# espnative-deadrail-2-d.net
KiCad netlist of a schematic drawn in EAGLE
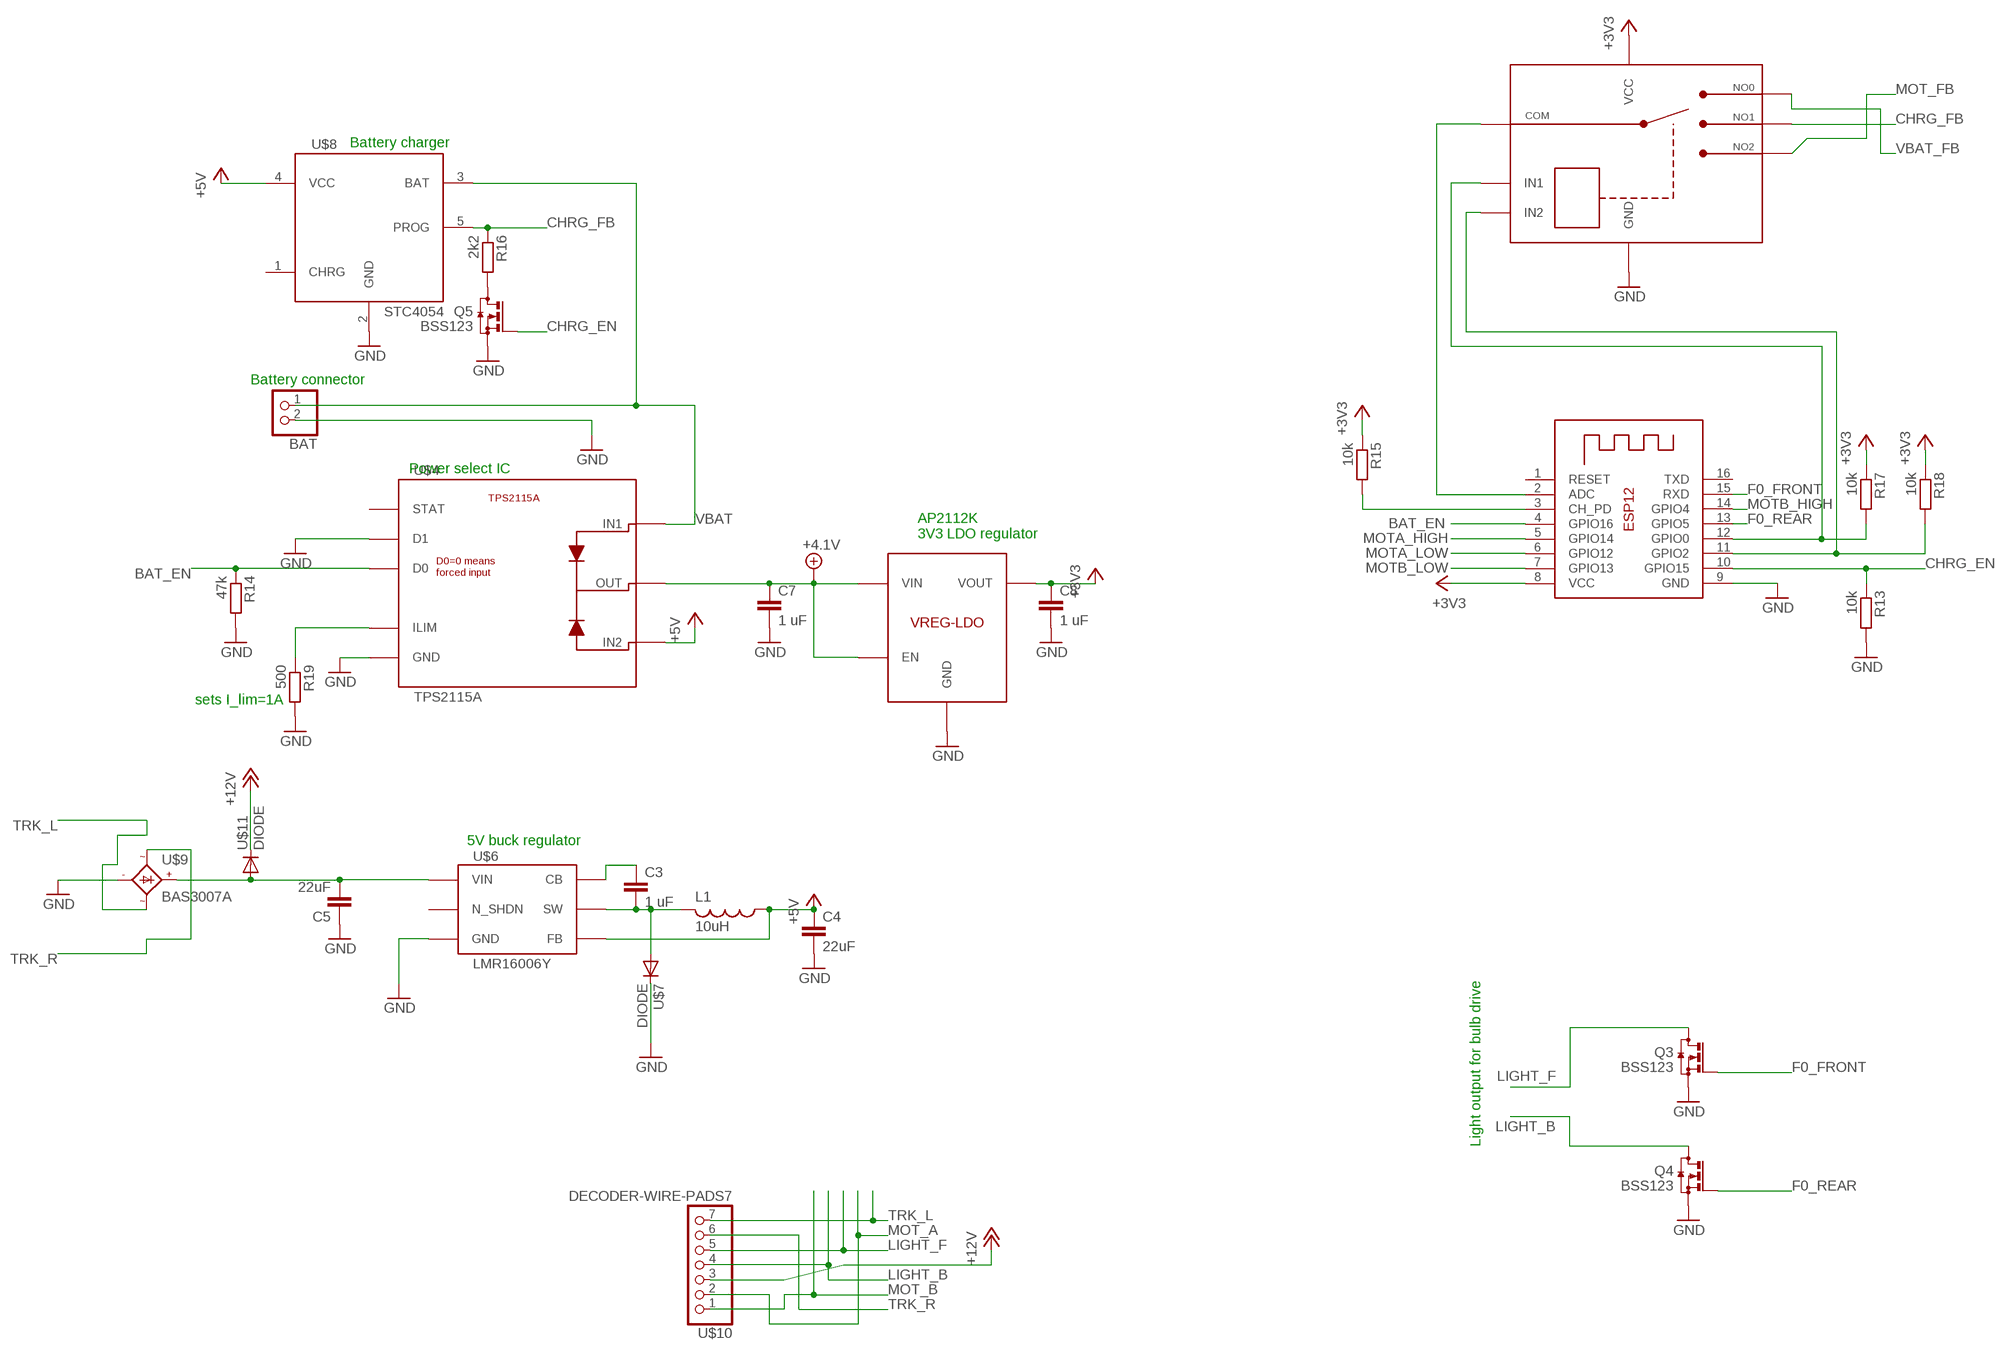
[diagram p0: schematic, sheet 1, part 1 of 2]
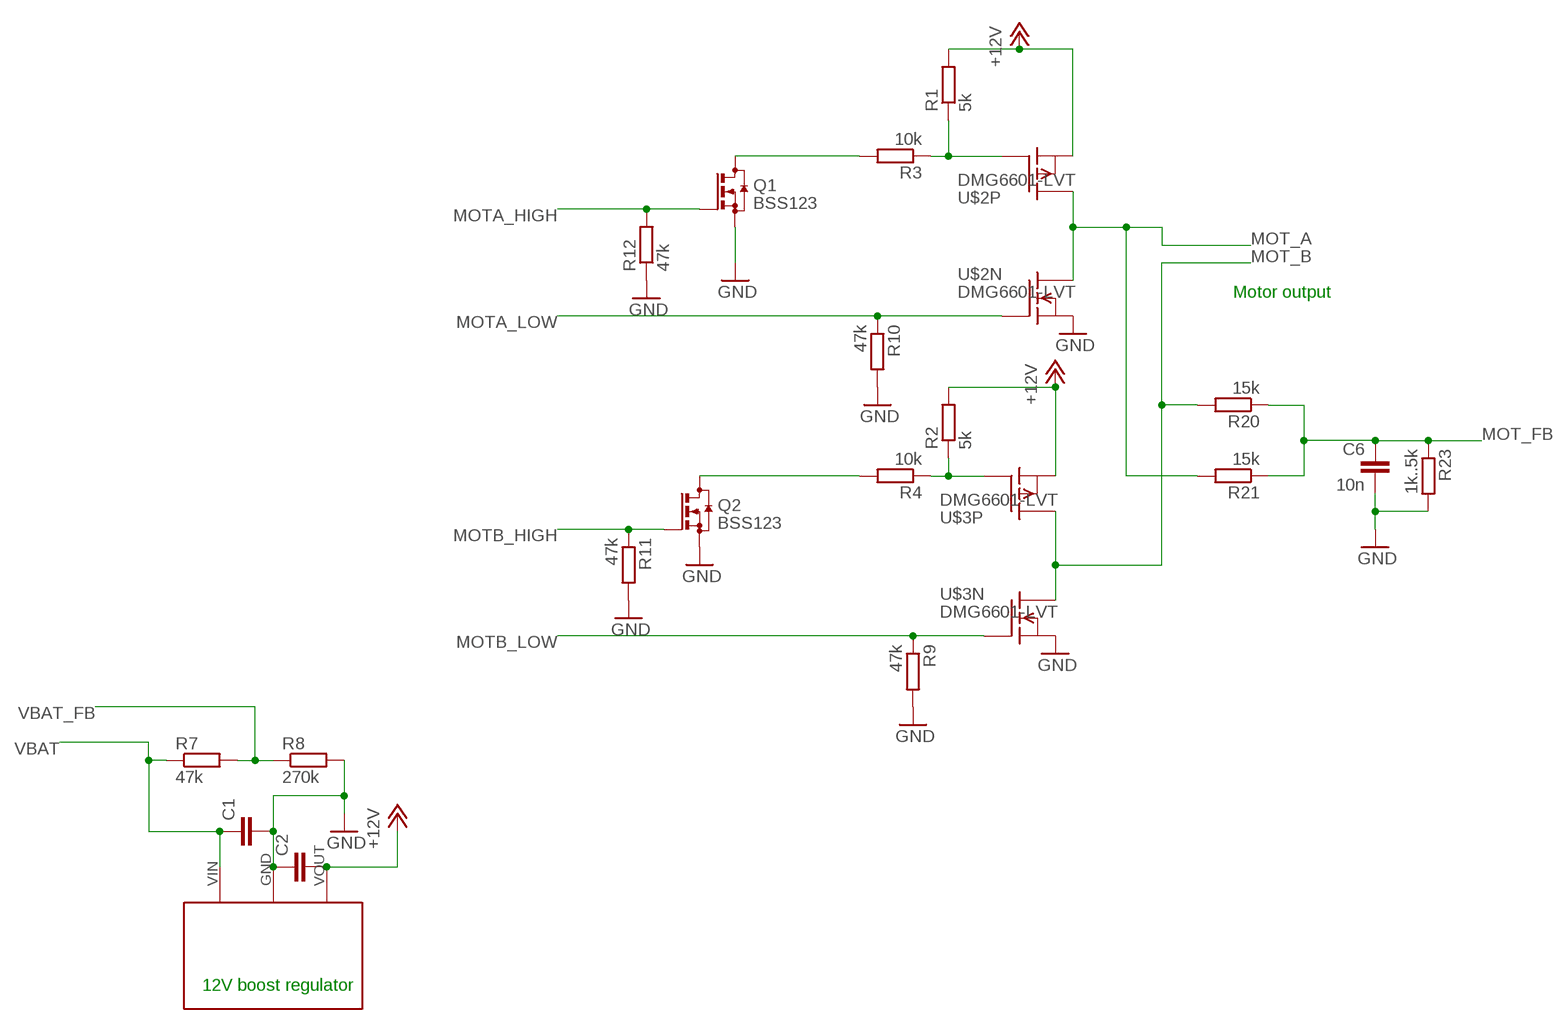
[diagram p1: schematic, sheet 1, part 2 of 2]

(export (version "E")
  (design (tool "Eeschema 10.0.6"))
  (components
    (comp (ref "BAT")
      (value "JST_2PIN-SMT-RA")
      (footprint "eagle-import:JST-PH-2-SMT-RA")
      (libsource (lib "eagle-import") (part "JST_2PIN-SMT-RA"))
    )
    (comp (ref "C1")
      (value "C-EUC1206")
      (footprint "eagle-import:C1206")
      (libsource (lib "eagle-import") (part "C-EUC1206"))
    )
    (comp (ref "C2")
      (value "C-EUC1206")
      (footprint "eagle-import:C1206")
      (libsource (lib "eagle-import") (part "C-EUC1206"))
    )
    (comp (ref "C3")
      (value "1 uF")
      (footprint "eagle-import:C0603")
      (libsource (lib "eagle-import") (part "C-EUC0603"))
    )
    (comp (ref "C4")
      (value "22uF")
      (footprint "eagle-import:C0603")
      (libsource (lib "eagle-import") (part "C-EUC0603"))
    )
    (comp (ref "C5")
      (value "22uF")
      (footprint "eagle-import:C1206")
      (libsource (lib "eagle-import") (part "C-EUC1206"))
    )
    (comp (ref "C6")
      (value "10n")
      (footprint "eagle-import:C0603")
      (libsource (lib "eagle-import") (part "C-EUC0603"))
    )
    (comp (ref "C7")
      (value "1 uF")
      (footprint "eagle-import:C0603")
      (libsource (lib "eagle-import") (part "C-EUC0603"))
    )
    (comp (ref "C8")
      (value "1 uF")
      (footprint "eagle-import:C0603")
      (libsource (lib "eagle-import") (part "C-EUC0603"))
    )
    (comp (ref "L1")
      (value "10uH")
      (footprint "eagle-import:FDSD0420")
      (libsource (lib "eagle-import") (part "FDSD0420"))
    )
    (comp (ref "Q1")
      (value "BSS123")
      (footprint "eagle-import:SOT23")
      (libsource (lib "eagle-import") (part "BSS123"))
    )
    (comp (ref "Q2")
      (value "BSS123")
      (footprint "eagle-import:SOT23")
      (libsource (lib "eagle-import") (part "BSS123"))
    )
    (comp (ref "Q3")
      (value "BSS123")
      (footprint "eagle-import:SOT23")
      (libsource (lib "eagle-import") (part "BSS123"))
    )
    (comp (ref "Q4")
      (value "BSS123")
      (footprint "eagle-import:SOT23")
      (libsource (lib "eagle-import") (part "BSS123"))
    )
    (comp (ref "Q5")
      (value "BSS123")
      (footprint "eagle-import:SOT23")
      (libsource (lib "eagle-import") (part "BSS123"))
    )
    (comp (ref "R1")
      (value "5k")
      (footprint "eagle-import:R0603")
      (libsource (lib "eagle-import") (part "R-EU_R0603"))
    )
    (comp (ref "R2")
      (value "5k")
      (footprint "eagle-import:R0603")
      (libsource (lib "eagle-import") (part "R-EU_R0603"))
    )
    (comp (ref "R3")
      (value "10k")
      (footprint "eagle-import:R0603")
      (libsource (lib "eagle-import") (part "R-EU_R0603"))
    )
    (comp (ref "R4")
      (value "10k")
      (footprint "eagle-import:R0603")
      (libsource (lib "eagle-import") (part "R-EU_R0603"))
    )
    (comp (ref "R7")
      (value "47k")
      (footprint "eagle-import:R0603")
      (libsource (lib "eagle-import") (part "R-EU_R0603"))
    )
    (comp (ref "R8")
      (value "270k")
      (footprint "eagle-import:R0603")
      (libsource (lib "eagle-import") (part "R-EU_R0603"))
    )
    (comp (ref "R9")
      (value "47k")
      (footprint "eagle-import:R0603")
      (libsource (lib "eagle-import") (part "R-EU_R0603"))
    )
    (comp (ref "R10")
      (value "47k")
      (footprint "eagle-import:R0603")
      (libsource (lib "eagle-import") (part "R-EU_R0603"))
    )
    (comp (ref "R11")
      (value "47k")
      (footprint "eagle-import:R0603")
      (libsource (lib "eagle-import") (part "R-EU_R0603"))
    )
    (comp (ref "R12")
      (value "47k")
      (footprint "eagle-import:R0603")
      (libsource (lib "eagle-import") (part "R-EU_R0603"))
    )
    (comp (ref "R13")
      (value "10k")
      (footprint "eagle-import:R0603")
      (libsource (lib "eagle-import") (part "R-EU_R0603"))
    )
    (comp (ref "R14")
      (value "47k")
      (footprint "eagle-import:R0603")
      (libsource (lib "eagle-import") (part "R-EU_R0603"))
    )
    (comp (ref "R15")
      (value "10k")
      (footprint "eagle-import:R0603")
      (libsource (lib "eagle-import") (part "R-EU_R0603"))
    )
    (comp (ref "R16")
      (value "2k2")
      (footprint "eagle-import:R0603")
      (libsource (lib "eagle-import") (part "R-EU_R0603"))
    )
    (comp (ref "R17")
      (value "10k")
      (footprint "eagle-import:R0603")
      (libsource (lib "eagle-import") (part "R-EU_R0603"))
    )
    (comp (ref "R18")
      (value "10k")
      (footprint "eagle-import:R0603")
      (libsource (lib "eagle-import") (part "R-EU_R0603"))
    )
    (comp (ref "R19")
      (value "500")
      (footprint "eagle-import:R0603")
      (libsource (lib "eagle-import") (part "R-EU_R0603"))
    )
    (comp (ref "R20")
      (value "15k")
      (footprint "eagle-import:R0603")
      (libsource (lib "eagle-import") (part "R-EU_R0603"))
    )
    (comp (ref "R21")
      (value "15k")
      (footprint "eagle-import:R0603")
      (libsource (lib "eagle-import") (part "R-EU_R0603"))
    )
    (comp (ref "R23")
      (value "1k..5k")
      (footprint "eagle-import:R0603")
      (libsource (lib "eagle-import") (part "R-EU_R0603"))
    )
    (comp (ref "U$1")
      (value "AP2112K-3V3")
      (footprint "eagle-import:SOT23-5L")
      (libsource (lib "eagle-import") (part "AP2112K"))
    )
    (comp (ref "U$2")
      (value "DMG6601-LVT")
      (footprint "eagle-import:TSOT-26")
      (libsource (lib "eagle-import") (part "DMG6601-LVT"))
    )
    (comp (ref "U$3")
      (value "DMG6601-LVT")
      (footprint "eagle-import:TSOT-26")
      (libsource (lib "eagle-import") (part "DMG6601-LVT"))
    )
    (comp (ref "U$4")
      (value "TPS2115A")
      (footprint "eagle-import:TSSOP-8")
      (libsource (lib "eagle-import") (part "TPS2115A"))
    )
    (comp (ref "U$5")
      (value "POLOLU-VREG12")
      (footprint "eagle-import:POLOLU-REGULATOR")
      (libsource (lib "eagle-import") (part "POLOLU-VREG12"))
    )
    (comp (ref "U$6")
      (value "LMR16006Y")
      (footprint "eagle-import:SOT23-6")
      (libsource (lib "eagle-import") (part "LMR16006Y"))
    )
    (comp (ref "U$7")
      (value "DIODE")
      (footprint "eagle-import:DIODE-1206")
      (libsource (lib "eagle-import") (part "DIODE"))
    )
    (comp (ref "U$8")
      (value "STC4054")
      (footprint "eagle-import:SOT23-5L")
      (libsource (lib "eagle-import") (part "STC4054"))
    )
    (comp (ref "U$9")
      (value "BAS3007A")
      (footprint "eagle-import:SOT143B")
      (libsource (lib "eagle-import") (part "BAS3007A"))
    )
    (comp (ref "U$10")
      (value "DECODER-WIRE-PADS7")
      (footprint "eagle-import:DECODER-WIRE-PADS")
      (libsource (lib "eagle-import") (part "DECODER-WIRE-PADS7"))
    )
    (comp (ref "U$11")
      (value "DIODE")
      (footprint "eagle-import:DIODE-1206")
      (libsource (lib "eagle-import") (part "DIODE"))
    )
    (comp (ref "U$12")
      (value "TS5A3359")
      (footprint "eagle-import:US8")
      (libsource (lib "eagle-import") (part "TS5A3359"))
    )
    (comp (ref "X1")
      (value "ESP-12")
      (footprint "eagle-import:ESP-12")
      (libsource (lib "eagle-import") (part "ESP-12"))
    )
  )
  (nets
    (net (code "1") (name "+3V3") (class "Default")
      (node (ref "C8") (pin "1") (pinfunction "1_1") (pintype "passive"))
      (node (ref "R15") (pin "1") (pinfunction "1_1") (pintype "passive"))
      (node (ref "R17") (pin "1") (pinfunction "1_1") (pintype "passive"))
      (node (ref "R18") (pin "1") (pinfunction "1_1") (pintype "passive"))
      (node (ref "U$1") (pin "5") (pinfunction "VOUT_5") (pintype "bidirectional"))
      (node (ref "U$12") (pin "8") (pinfunction "VCC_8") (pintype "bidirectional"))
      (node (ref "X1") (pin "8") (pinfunction "VCC_8") (pintype "power_in"))
    )
    (net (code "2") (name "+4.1V") (class "Default")
      (node (ref "C7") (pin "1") (pinfunction "1_1") (pintype "passive"))
      (node (ref "U$1") (pin "1") (pinfunction "VIN_1") (pintype "bidirectional"))
      (node (ref "U$1") (pin "3") (pinfunction "EN_3") (pintype "bidirectional"))
      (node (ref "U$4") (pin "7") (pinfunction "OUT_7") (pintype "bidirectional"))
    )
    (net (code "3") (name "+5V") (class "Default")
      (node (ref "C4") (pin "1") (pinfunction "1_1") (pintype "passive"))
      (node (ref "L1") (pin "P$1") (pinfunction "1_P$1") (pintype "passive"))
      (node (ref "U$4") (pin "6") (pinfunction "IN2_6") (pintype "bidirectional"))
      (node (ref "U$6") (pin "3") (pinfunction "FB_3") (pintype "bidirectional"))
      (node (ref "U$8") (pin "4") (pinfunction "VCC_4") (pintype "bidirectional"))
    )
    (net (code "4") (name "+12V") (class "Default")
      (node (ref "C2") (pin "2") (pinfunction "2_2") (pintype "passive"))
      (node (ref "R1") (pin "2") (pinfunction "2_2") (pintype "passive"))
      (node (ref "R2") (pin "2") (pinfunction "2_2") (pintype "passive"))
      (node (ref "U$10") (pin "3") (pinfunction "3_3") (pintype "passive"))
      (node (ref "U$11") (pin "C") (pinfunction "C_C") (pintype "passive"))
      (node (ref "U$2") (pin "2") (pinfunction "S_2") (pintype "passive"))
      (node (ref "U$3") (pin "2") (pinfunction "S_2") (pintype "passive"))
      (node (ref "U$5") (pin "VOUT") (pinfunction "VOUT_VOUT") (pintype "bidirectional"))
    )
    (net (code "5") (name "/BAT_EN") (class "Default")
      (node (ref "R14") (pin "1") (pinfunction "1_1") (pintype "passive"))
      (node (ref "U$4") (pin "2") (pinfunction "D0_2") (pintype "bidirectional"))
      (node (ref "X1") (pin "4") (pinfunction "GPIO16_4") (pintype "bidirectional"))
    )
    (net (code "6") (name "/CHRG_EN") (class "Default")
      (node (ref "Q5") (pin "1") (pinfunction "G_1") (pintype "passive"))
      (node (ref "R13") (pin "1") (pinfunction "1_1") (pintype "passive"))
      (node (ref "X1") (pin "10") (pinfunction "GPIO15_10") (pintype "bidirectional"))
    )
    (net (code "7") (name "/CHRG_FB") (class "Default")
      (node (ref "R16") (pin "1") (pinfunction "1_1") (pintype "passive"))
      (node (ref "U$12") (pin "2") (pinfunction "NO1_2") (pintype "bidirectional"))
      (node (ref "U$8") (pin "5") (pinfunction "PROG_5") (pintype "bidirectional"))
    )
    (net (code "8") (name "/F0_FRONT") (class "Default")
      (node (ref "Q3") (pin "1") (pinfunction "G_1") (pintype "passive"))
      (node (ref "X1") (pin "15") (pinfunction "RXD_15") (pintype "input"))
    )
    (net (code "9") (name "/F0_REAR") (class "Default")
      (node (ref "Q4") (pin "1") (pinfunction "G_1") (pintype "passive"))
      (node (ref "X1") (pin "13") (pinfunction "GPIO5_13") (pintype "bidirectional"))
    )
    (net (code "10") (name "/LIGHT_B") (class "Default")
      (node (ref "Q4") (pin "3") (pinfunction "D_3") (pintype "passive"))
      (node (ref "U$10") (pin "4") (pinfunction "4_4") (pintype "passive"))
    )
    (net (code "11") (name "/LIGHT_F") (class "Default")
      (node (ref "Q3") (pin "3") (pinfunction "D_3") (pintype "passive"))
      (node (ref "U$10") (pin "5") (pinfunction "5_5") (pintype "passive"))
    )
    (net (code "12") (name "/MOTA_HIGH") (class "Default")
      (node (ref "Q1") (pin "1") (pinfunction "G_1") (pintype "passive"))
      (node (ref "R12") (pin "2") (pinfunction "2_2") (pintype "passive"))
      (node (ref "X1") (pin "5") (pinfunction "GPIO14_5") (pintype "bidirectional"))
    )
    (net (code "13") (name "/MOTA_LOW") (class "Default")
      (node (ref "R10") (pin "1") (pinfunction "1_1") (pintype "passive"))
      (node (ref "U$2") (pin "1") (pinfunction "G_1") (pintype "passive"))
      (node (ref "X1") (pin "6") (pinfunction "GPIO12_6") (pintype "bidirectional"))
    )
    (net (code "14") (name "/MOTB_HIGH") (class "Default")
      (node (ref "Q2") (pin "1") (pinfunction "G_1") (pintype "passive"))
      (node (ref "R11") (pin "1") (pinfunction "1_1") (pintype "passive"))
      (node (ref "X1") (pin "14") (pinfunction "GPIO4_14") (pintype "bidirectional"))
    )
    (net (code "15") (name "/MOTB_LOW") (class "Default")
      (node (ref "R9") (pin "1") (pinfunction "1_1") (pintype "passive"))
      (node (ref "U$3") (pin "1") (pinfunction "G_1") (pintype "passive"))
      (node (ref "X1") (pin "7") (pinfunction "GPIO13_7") (pintype "bidirectional"))
    )
    (net (code "16") (name "/MOT_A") (class "Default")
      (node (ref "R21") (pin "2") (pinfunction "2_2") (pintype "passive"))
      (node (ref "U$10") (pin "2") (pinfunction "2_2") (pintype "passive"))
      (node (ref "U$2") (pin "4") (pinfunction "D_4") (pintype "passive"))
      (node (ref "U$2") (pin "6") (pinfunction "D_6") (pintype "passive"))
    )
    (net (code "17") (name "/MOT_B") (class "Default")
      (node (ref "R20") (pin "2") (pinfunction "2_2") (pintype "passive"))
      (node (ref "U$10") (pin "1") (pinfunction "1_1") (pintype "passive"))
      (node (ref "U$3") (pin "4") (pinfunction "D_4") (pintype "passive"))
      (node (ref "U$3") (pin "6") (pinfunction "D_6") (pintype "passive"))
    )
    (net (code "18") (name "/MOT_FB") (class "Default")
      (node (ref "C6") (pin "1") (pinfunction "1_1") (pintype "passive"))
      (node (ref "R20") (pin "1") (pinfunction "1_1") (pintype "passive"))
      (node (ref "R21") (pin "1") (pinfunction "1_1") (pintype "passive"))
      (node (ref "R23") (pin "1") (pinfunction "1_1") (pintype "passive"))
      (node (ref "U$12") (pin "3") (pinfunction "NO2_3") (pintype "bidirectional"))
    )
    (net (code "19") (name "/TRK_L") (class "Default")
      (node (ref "U$10") (pin "7") (pinfunction "7_7") (pintype "passive"))
      (node (ref "U$9") (pin "3") (pinfunction "AC2_3") (pintype "passive"))
    )
    (net (code "20") (name "/TRK_R") (class "Default")
      (node (ref "U$10") (pin "6") (pinfunction "6_6") (pintype "passive"))
      (node (ref "U$9") (pin "2") (pinfunction "AC1_2") (pintype "passive"))
    )
    (net (code "21") (name "/VBAT") (class "Default")
      (node (ref "BAT") (pin "1") (pinfunction "2_1") (pintype "passive"))
      (node (ref "C1") (pin "1") (pinfunction "1_1") (pintype "passive"))
      (node (ref "R7") (pin "1") (pinfunction "1_1") (pintype "passive"))
      (node (ref "U$4") (pin "8") (pinfunction "IN1_8") (pintype "bidirectional"))
      (node (ref "U$5") (pin "VIN") (pinfunction "VIN_VIN") (pintype "bidirectional"))
      (node (ref "U$8") (pin "3") (pinfunction "BAT_3") (pintype "bidirectional"))
    )
    (net (code "22") (name "/VBAT_FB") (class "Default")
      (node (ref "R7") (pin "2") (pinfunction "2_2") (pintype "passive"))
      (node (ref "R8") (pin "1") (pinfunction "1_1") (pintype "passive"))
      (node (ref "U$12") (pin "1") (pinfunction "NO0_1") (pintype "bidirectional"))
    )
    (net (code "23") (name "GND") (class "Default")
      (node (ref "BAT") (pin "2") (pinfunction "1_2") (pintype "passive"))
      (node (ref "C1") (pin "2") (pinfunction "2_2") (pintype "passive"))
      (node (ref "C2") (pin "1") (pinfunction "1_1") (pintype "passive"))
      (node (ref "C4") (pin "2") (pinfunction "2_2") (pintype "passive"))
      (node (ref "C5") (pin "1") (pinfunction "1_1") (pintype "passive"))
      (node (ref "C6") (pin "2") (pinfunction "2_2") (pintype "passive"))
      (node (ref "C7") (pin "2") (pinfunction "2_2") (pintype "passive"))
      (node (ref "C8") (pin "2") (pinfunction "2_2") (pintype "passive"))
      (node (ref "Q1") (pin "2") (pinfunction "S_2") (pintype "passive"))
      (node (ref "Q2") (pin "2") (pinfunction "S_2") (pintype "passive"))
      (node (ref "Q3") (pin "2") (pinfunction "S_2") (pintype "passive"))
      (node (ref "Q4") (pin "2") (pinfunction "S_2") (pintype "passive"))
      (node (ref "Q5") (pin "2") (pinfunction "S_2") (pintype "passive"))
      (node (ref "R10") (pin "2") (pinfunction "2_2") (pintype "passive"))
      (node (ref "R11") (pin "2") (pinfunction "2_2") (pintype "passive"))
      (node (ref "R12") (pin "1") (pinfunction "1_1") (pintype "passive"))
      (node (ref "R13") (pin "2") (pinfunction "2_2") (pintype "passive"))
      (node (ref "R14") (pin "2") (pinfunction "2_2") (pintype "passive"))
      (node (ref "R19") (pin "2") (pinfunction "2_2") (pintype "passive"))
      (node (ref "R23") (pin "2") (pinfunction "2_2") (pintype "passive"))
      (node (ref "R8") (pin "2") (pinfunction "2_2") (pintype "passive"))
      (node (ref "R9") (pin "2") (pinfunction "2_2") (pintype "passive"))
      (node (ref "U$1") (pin "2") (pinfunction "GND_2") (pintype "bidirectional"))
      (node (ref "U$12") (pin "4") (pinfunction "GND_4") (pintype "bidirectional"))
      (node (ref "U$2") (pin "5") (pinfunction "S_5") (pintype "passive"))
      (node (ref "U$3") (pin "5") (pinfunction "S_5") (pintype "passive"))
      (node (ref "U$4") (pin "3") (pinfunction "D1_3") (pintype "bidirectional"))
      (node (ref "U$4") (pin "5") (pinfunction "GND_5") (pintype "bidirectional"))
      (node (ref "U$5") (pin "GND") (pinfunction "GND_GND") (pintype "bidirectional"))
      (node (ref "U$6") (pin "2") (pinfunction "GND_2") (pintype "bidirectional"))
      (node (ref "U$7") (pin "C") (pinfunction "C_C") (pintype "passive"))
      (node (ref "U$8") (pin "2") (pinfunction "GND_2") (pintype "bidirectional"))
      (node (ref "U$9") (pin "1") (pinfunction "-_1") (pintype "passive"))
      (node (ref "X1") (pin "9") (pinfunction "GND_9") (pintype "power_in"))
    )
    (net (code "24") (name "Net-(L1-2)") (class "Default")
      (node (ref "C3") (pin "2") (pinfunction "2_2") (pintype "passive"))
      (node (ref "L1") (pin "P$2") (pinfunction "2_P$2") (pintype "passive"))
      (node (ref "U$6") (pin "6") (pinfunction "SW_6") (pintype "bidirectional"))
      (node (ref "U$7") (pin "A") (pinfunction "A_A") (pintype "passive"))
    )
    (net (code "25") (name "Net-(Q1-D)") (class "Default")
      (node (ref "Q1") (pin "3") (pinfunction "D_3") (pintype "passive"))
      (node (ref "R3") (pin "2") (pinfunction "2_2") (pintype "passive"))
    )
    (net (code "26") (name "Net-(Q2-D)") (class "Default")
      (node (ref "Q2") (pin "3") (pinfunction "D_3") (pintype "passive"))
      (node (ref "R4") (pin "2") (pinfunction "2_2") (pintype "passive"))
    )
    (net (code "27") (name "Net-(Q5-D)") (class "Default")
      (node (ref "Q5") (pin "3") (pinfunction "D_3") (pintype "passive"))
      (node (ref "R16") (pin "2") (pinfunction "2_2") (pintype "passive"))
    )
    (net (code "28") (name "Net-(U$2B-G)") (class "Default")
      (node (ref "R1") (pin "1") (pinfunction "1_1") (pintype "passive"))
      (node (ref "R3") (pin "1") (pinfunction "1_1") (pintype "passive"))
      (node (ref "U$2") (pin "3") (pinfunction "G_3") (pintype "passive"))
    )
    (net (code "29") (name "Net-(U$3B-G)") (class "Default")
      (node (ref "R2") (pin "1") (pinfunction "1_1") (pintype "passive"))
      (node (ref "R4") (pin "1") (pinfunction "1_1") (pintype "passive"))
      (node (ref "U$3") (pin "3") (pinfunction "G_3") (pintype "passive"))
    )
    (net (code "30") (name "Net-(U$4-ILIM)") (class "Default")
      (node (ref "R19") (pin "1") (pinfunction "1_1") (pintype "passive"))
      (node (ref "U$4") (pin "4") (pinfunction "ILIM_4") (pintype "bidirectional"))
    )
    (net (code "31") (name "Net-(U$6-CB)") (class "Default")
      (node (ref "C3") (pin "1") (pinfunction "1_1") (pintype "passive"))
      (node (ref "U$6") (pin "1") (pinfunction "CB_1") (pintype "bidirectional"))
    )
    (net (code "32") (name "Net-(U$6-VIN)") (class "Default")
      (node (ref "C5") (pin "2") (pinfunction "2_2") (pintype "passive"))
      (node (ref "U$11") (pin "A") (pinfunction "A_A") (pintype "passive"))
      (node (ref "U$6") (pin "5") (pinfunction "VIN_5") (pintype "bidirectional"))
      (node (ref "U$9") (pin "4") (pinfunction "+_4") (pintype "passive"))
    )
    (net (code "33") (name "Net-(U$12-COM)") (class "Default")
      (node (ref "U$12") (pin "7") (pinfunction "COM_7") (pintype "bidirectional"))
      (node (ref "X1") (pin "2") (pinfunction "ADC_2") (pintype "passive"))
    )
    (net (code "34") (name "Net-(U$12-IN1)") (class "Default")
      (node (ref "R17") (pin "2") (pinfunction "2_2") (pintype "passive"))
      (node (ref "U$12") (pin "6") (pinfunction "IN1_6") (pintype "bidirectional"))
      (node (ref "X1") (pin "12") (pinfunction "GPIO0_12") (pintype "bidirectional"))
    )
    (net (code "35") (name "Net-(U$12-IN2)") (class "Default")
      (node (ref "R18") (pin "2") (pinfunction "2_2") (pintype "passive"))
      (node (ref "U$12") (pin "5") (pinfunction "IN2_5") (pintype "bidirectional"))
      (node (ref "X1") (pin "11") (pinfunction "GPIO2_11") (pintype "bidirectional"))
    )
    (net (code "36") (name "Net-(X1-CH_PD)") (class "Default")
      (node (ref "R15") (pin "2") (pinfunction "2_2") (pintype "passive"))
      (node (ref "X1") (pin "3") (pinfunction "CH_PD_3") (pintype "input"))
    )
    (net (code "37") (name "unconnected-(U$4-STAT-Pad1)") (class "Default")
      (node (ref "U$4") (pin "1") (pinfunction "STAT_1") (pintype "bidirectional"))
    )
    (net (code "38") (name "unconnected-(U$6-N_SHDN-Pad4)") (class "Default")
      (node (ref "U$6") (pin "4") (pinfunction "N_SHDN_4") (pintype "bidirectional"))
    )
    (net (code "39") (name "unconnected-(U$8-CHRG-Pad1)") (class "Default")
      (node (ref "U$8") (pin "1") (pinfunction "CHRG_1") (pintype "bidirectional"))
    )
    (net (code "40") (name "unconnected-(X1-RESET-Pad1)") (class "Default")
      (node (ref "X1") (pin "1") (pinfunction "RESET_1") (pintype "input"))
    )
    (net (code "41") (name "unconnected-(X1-TXD-Pad16)") (class "Default")
      (node (ref "X1") (pin "16") (pinfunction "TXD_16") (pintype "output"))
    )
  )
)
